# 03_MCU.net
KiCad netlist of a schematic drawn in Altium Designer
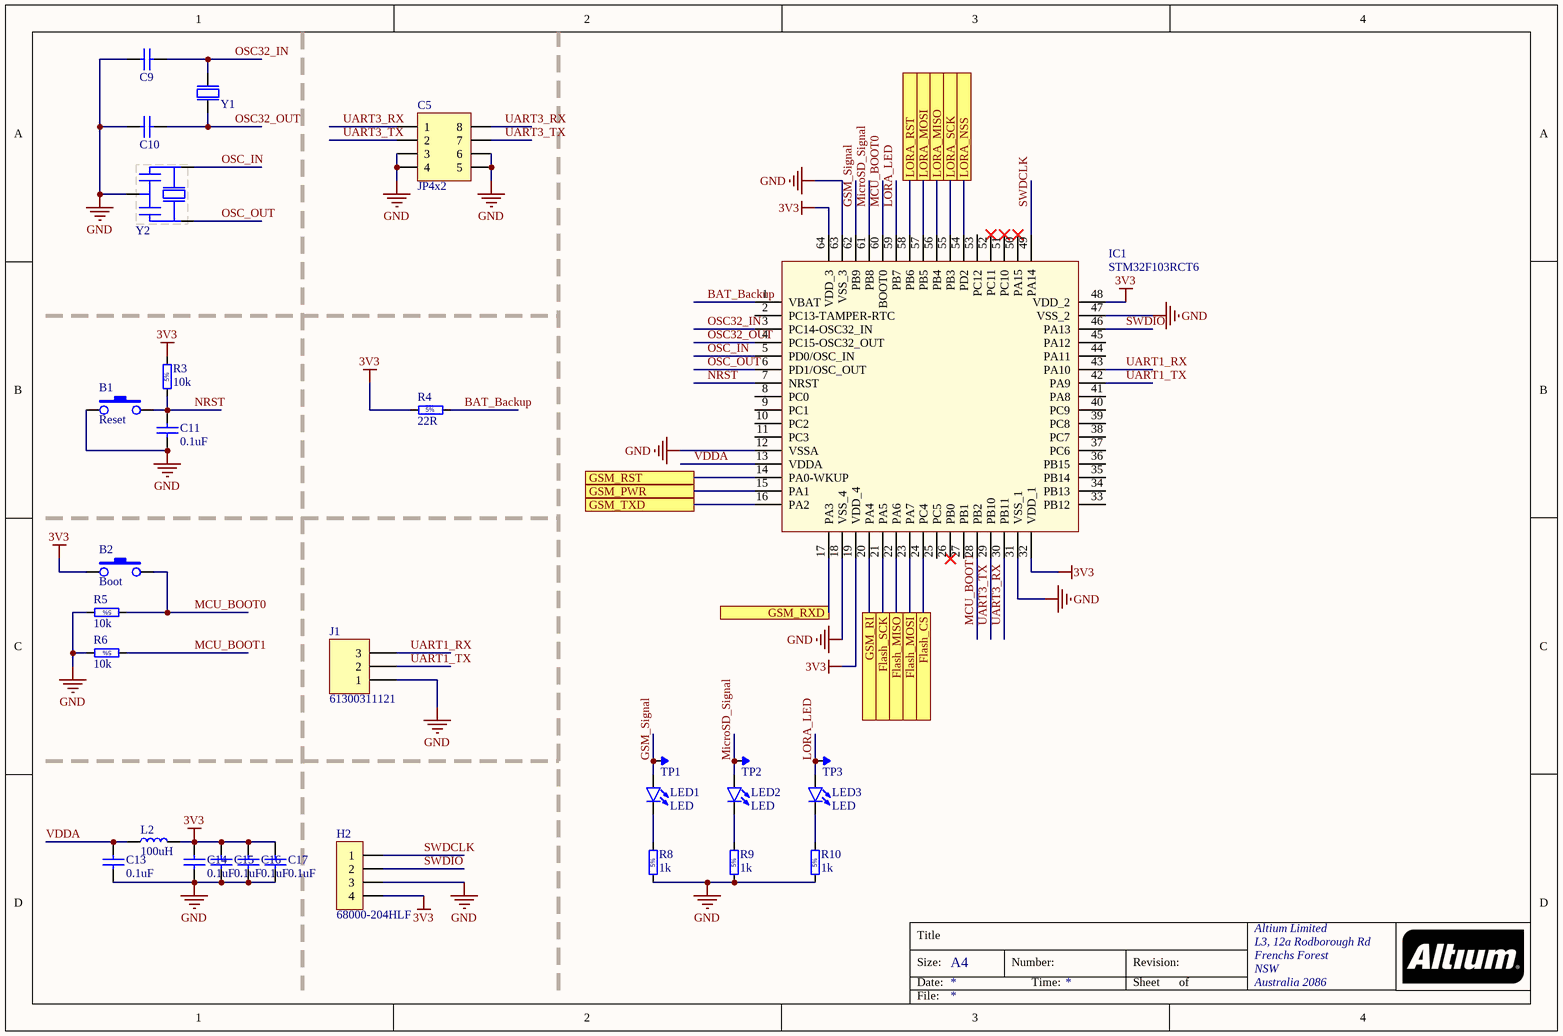
[diagram p0: [03].MCU.SchDoc]

(export (version "E")
  (design (tool "Eeschema 10.0.6"))
  (components
    (comp (ref "B1")
      (value "Reset")
      (footprint "TACTILE-SWITCH-1101NE")
      (libsource (lib "ThanhNT") (part "Button_2P_SMD"))
    )
    (comp (ref "B2")
      (value "Boot")
      (footprint "TACTILE-SWITCH-1101NE")
      (libsource (lib "ThanhNT") (part "Button_2P_SMD"))
    )
    (comp (ref "C5")
      (value "JP4x2")
      (footprint "JP4-D2T")
      (description "WR-PHD 2.54 mm Dual Socket Header")
      (fields
        (field (name "MANUFACTURER") "Würth Elektronik eiSos GmbH")
        (field (name "PARTNO") "61300821821")
        (field (name "CREATED BY") "Karrer Zheng")
      )
      (libsource (lib "LIBRARY") (part "JP4x2"))
    )
    (comp (ref "C9")
      (value "10pF")
      (footprint "C_0603")
      (description "Non-polarised capacitor")
      (fields (field (name "PART NUMBER") "VJ0805A100JXJPW1BC") (field (name "VOLTAGE") "16VDC"))
      (libsource (lib "Capacitors") (part "Capacitor - non polarized"))
    )
    (comp (ref "C10")
      (value "10pF")
      (footprint "C_0603")
      (description "Non-polarised capacitor")
      (fields (field (name "PART NUMBER") "VJ0805A100JXJPW1BC") (field (name "VOLTAGE") "16VDC"))
      (libsource (lib "Capacitors") (part "Capacitor - non polarized"))
    )
    (comp (ref "C11")
      (value "0.1uF")
      (footprint "C_0603")
      (description "Non-polarised capacitor")
      (fields (field (name "PART NUMBER") "VJ0805Y104KXXMC") (field (name "VOLTAGE") "25VDC"))
      (libsource (lib "Capacitors") (part "Capacitor - non polarized"))
    )
    (comp (ref "C13")
      (value "0.1uF")
      (footprint "C_0603")
      (description "Non-polarised capacitor")
      (fields (field (name "PART NUMBER") "VJ0805Y104KXXMC") (field (name "VOLTAGE") "25VDC"))
      (libsource (lib "Capacitors") (part "Capacitor - non polarized"))
    )
    (comp (ref "C14")
      (value "0.1uF")
      (footprint "C_0603")
      (description "Non-polarised capacitor")
      (fields (field (name "PART NUMBER") "VJ0805Y104KXXMC") (field (name "VOLTAGE") "25VDC"))
      (libsource (lib "Capacitors") (part "Capacitor - non polarized"))
    )
    (comp (ref "C15")
      (value "0.1uF")
      (footprint "C_0603")
      (description "Non-polarised capacitor")
      (fields (field (name "PART NUMBER") "VJ0805Y104KXXMC") (field (name "VOLTAGE") "25VDC"))
      (libsource (lib "Capacitors") (part "Capacitor - non polarized"))
    )
    (comp (ref "C16")
      (value "0.1uF")
      (footprint "C_0603")
      (description "Non-polarised capacitor")
      (fields (field (name "PART NUMBER") "VJ0805Y104KXXMC") (field (name "VOLTAGE") "25VDC"))
      (libsource (lib "Capacitors") (part "Capacitor - non polarized"))
    )
    (comp (ref "C17")
      (value "0.1uF")
      (footprint "C_0603")
      (description "Non-polarised capacitor")
      (fields (field (name "PART NUMBER") "VJ0805Y104KXXMC") (field (name "VOLTAGE") "25VDC"))
      (libsource (lib "Capacitors") (part "Capacitor - non polarized"))
    )
    (comp (ref "H2")
      (value "68000-204HLF")
      (footprint "HDR1X4")
      (description "CONN HEADER 4POS .100 STR 15AU")
      (fields
        (field (name "DEVICE") "68000-204HLF")
        (field (name "MANUFACTURER") "Amphenol FCI")
        (field (name "AUTHOR") "MDBK")
      )
      (libsource (lib "Eletro-mechanical") (part "Header_4p_2.54mm"))
    )
    (comp (ref "IC1")
      (value "STM32F103RCT6")
      (footprint "QFP50P1000X1000X160-64N")
      (description "ARM Microcontrollers - MCU 32BIT Cortex M3 H/D 256 to 512 USB/CAN")
      (fields
        (field (name "DEVICE") "STM32F103RCT6")
        (field (name "MANUFACTURER") "STMicroelectronics")
        (field (name "AUTHOR") "MDBK")
      )
      (libsource (lib "ICs And Semiconductors") (part "STM32F103RCT"))
    )
    (comp (ref "J1")
      (value "61300311121")
      (footprint "HDR1X3")
      (description "CONN HEADER 3 POS 2.54")
      (fields
        (field (name "DEVICE") "61300311121")
        (field (name "MANUFACTURER") "Wurth Electronics Inc.")
        (field (name "AUTHOR") "MDBK")
      )
      (libsource (lib "Eletro-mechanical") (part "Header_3p_2.54mm"))
    )
    (comp (ref "L2")
      (value "100uH")
      (footprint "Inductor_0805")
      (description "FIXED IND 100UH 80MA 5.5 OHM SMD")
      (fields
        (field (name "PART NUMBER") "LB2016T101M")
        (field (name "MANUFACTURER") "Taiyo Yuden")
        (field (name "AUTHOR") "MDBK")
      )
      (libsource (lib "Inductors & Transformers") (part "GLFR1608T101M-LR"))
    )
    (comp (ref "LED1") (value "LED") (footprint "LED_0805") (libsource (lib "ThanhNT") (part "LED_0805")))
    (comp (ref "LED2") (value "LED") (footprint "LED_0805") (libsource (lib "ThanhNT") (part "LED_0805")))
    (comp (ref "LED3") (value "LED") (footprint "LED_0805") (libsource (lib "ThanhNT") (part "LED_0805")))
    (comp (ref "R3")
      (value "10k")
      (footprint "R_0603")
      (description "Resistor - 5%")
      (fields
        (field (name "PART NUMBER") "RC0805FR-0710KL")
        (field (name "POWER") "125 mW (1/8 W)")
        (field (name "AUTHOR") "MDBK")
      )
      (libsource (lib "Resistors") (part "Resistor - 5%"))
    )
    (comp (ref "R4")
      (value "22R")
      (footprint "R_0603")
      (description "Resistor - 5%")
      (fields
        (field (name "PART NUMBER") "RC0805FR-0722RL")
        (field (name "POWER") "125 mW (1/8 W)")
        (field (name "AUTHOR") "MDBK")
      )
      (libsource (lib "Resistors") (part "Resistor - 5%"))
    )
    (comp (ref "R5")
      (value "10k")
      (footprint "R_0603")
      (description "Resistor - 5%")
      (fields
        (field (name "PART NUMBER") "RC0805FR-0710KL")
        (field (name "POWER") "125 mW (1/8 W)")
        (field (name "AUTHOR") "MDBK")
      )
      (libsource (lib "Resistors") (part "Resistor - 5%"))
    )
    (comp (ref "R6")
      (value "10k")
      (footprint "R_0603")
      (description "Resistor - 5%")
      (fields
        (field (name "PART NUMBER") "RC0805FR-0710KL")
        (field (name "POWER") "125 mW (1/8 W)")
        (field (name "AUTHOR") "MDBK")
      )
      (libsource (lib "Resistors") (part "Resistor - 5%"))
    )
    (comp (ref "R8")
      (value "1k")
      (footprint "R_0603")
      (description "Resistor - 5%")
      (fields
        (field (name "PART NUMBER") "RC0805JR-071KL")
        (field (name "POWER") "125 mW (1/8 W)")
        (field (name "AUTHOR") "MDBK")
      )
      (libsource (lib "Resistors") (part "Resistor - 5%"))
    )
    (comp (ref "R9")
      (value "1k")
      (footprint "R_0603")
      (description "Resistor - 5%")
      (fields
        (field (name "PART NUMBER") "RC0805JR-071KL")
        (field (name "POWER") "125 mW (1/8 W)")
        (field (name "AUTHOR") "MDBK")
      )
      (libsource (lib "Resistors") (part "Resistor - 5%"))
    )
    (comp (ref "R10")
      (value "1k")
      (footprint "R_0603")
      (description "Resistor - 5%")
      (fields
        (field (name "PART NUMBER") "RC0805JR-071KL")
        (field (name "POWER") "125 mW (1/8 W)")
        (field (name "AUTHOR") "MDBK")
      )
      (libsource (lib "Resistors") (part "Resistor - 5%"))
    )
    (comp (ref "TP1") (value "TESTPOINT") (footprint "TP-R40") (libsource (lib "ThanhNT") (part "TESTPOINT")))
    (comp (ref "TP2") (value "TESTPOINT") (footprint "TP-R40") (libsource (lib "ThanhNT") (part "TESTPOINT")))
    (comp (ref "TP3") (value "TESTPOINT") (footprint "TP-R40") (libsource (lib "ThanhNT") (part "TESTPOINT")))
    (comp (ref "Y1")
      (value "FC-135 32.7680KA-A0")
      (footprint "Crystal_2P")
      (description "CRYSTAL 32.7680KHZ 12.5PF SMT")
      (fields (field (name "MANUFACTURER") "EPSON") (field (name "AUTHOR") "MDBK"))
      (libsource (lib "Eletro-mechanical") (part "Crystal_32k"))
    )
    (comp (ref "Y2")
      (value "CSTCE8M00G52-R0")
      (footprint "Crystal_4P")
      (description "CER RES 8.0000MHZ 10PF SMD")
      (fields (field (name "MANUFACTURER") "Murata Electronics North America") (field (name "AUTHOR") "MDBK"))
      (libsource (lib "Eletro-mechanical") (part "Crystal-8MHz"))
    )
  )
  (nets
    (net (code "1") (name "/BAT_Backup") (class "Default")
      (node (ref "IC1") (pin "1") (pinfunction "VBAT_1") (pintype "passive"))
      (node (ref "R4") (pin "2") (pinfunction "2_2") (pintype "passive"))
    )
    (net (code "2") (name "/Flash_CS") (class "Default")
      (node (ref "IC1") (pin "24") (pinfunction "PC4_24") (pintype "passive"))
    )
    (net (code "3") (name "/Flash_MISO") (class "Default")
      (node (ref "IC1") (pin "22") (pinfunction "PA6_22") (pintype "passive"))
    )
    (net (code "4") (name "/Flash_MOSI") (class "Default")
      (node (ref "IC1") (pin "23") (pinfunction "PA7_23") (pintype "passive"))
    )
    (net (code "5") (name "/Flash_SCK") (class "Default")
      (node (ref "IC1") (pin "21") (pinfunction "PA5_21") (pintype "passive"))
    )
    (net (code "6") (name "/GSM_PWR") (class "Default")
      (node (ref "IC1") (pin "15") (pinfunction "PA1_15") (pintype "passive"))
    )
    (net (code "7") (name "/GSM_RI") (class "Default")
      (node (ref "IC1") (pin "20") (pinfunction "PA4_20") (pintype "passive"))
    )
    (net (code "8") (name "/GSM_RST") (class "Default")
      (node (ref "IC1") (pin "14") (pinfunction "PA0-WKUP_14") (pintype "passive"))
    )
    (net (code "9") (name "/GSM_RXD") (class "Default")
      (node (ref "IC1") (pin "17") (pinfunction "PA3_17") (pintype "passive"))
    )
    (net (code "10") (name "/GSM_Signal") (class "Default")
      (node (ref "IC1") (pin "62") (pinfunction "PB9_62") (pintype "passive"))
      (node (ref "LED1") (pin "A") (pinfunction "A_A") (pintype "passive"))
      (node (ref "TP1") (pin "1") (pintype "passive"))
    )
    (net (code "11") (name "/GSM_TXD") (class "Default")
      (node (ref "IC1") (pin "16") (pinfunction "PA2_16") (pintype "passive"))
    )
    (net (code "12") (name "/LORA_LED") (class "Default")
      (node (ref "IC1") (pin "59") (pinfunction "PB7_59") (pintype "passive"))
      (node (ref "LED3") (pin "A") (pinfunction "A_A") (pintype "passive"))
      (node (ref "TP3") (pin "1") (pintype "passive"))
    )
    (net (code "13") (name "/LORA_MISO") (class "Default")
      (node (ref "IC1") (pin "56") (pinfunction "PB4_56") (pintype "passive"))
    )
    (net (code "14") (name "/LORA_MOSI") (class "Default")
      (node (ref "IC1") (pin "57") (pinfunction "PB5_57") (pintype "passive"))
    )
    (net (code "15") (name "/LORA_NSS") (class "Default")
      (node (ref "IC1") (pin "54") (pinfunction "PD2_54") (pintype "passive"))
    )
    (net (code "16") (name "/LORA_RST") (class "Default")
      (node (ref "IC1") (pin "58") (pinfunction "PB6_58") (pintype "passive"))
    )
    (net (code "17") (name "/LORA_SCK") (class "Default")
      (node (ref "IC1") (pin "55") (pinfunction "PB3_55") (pintype "passive"))
    )
    (net (code "18") (name "/MCU_BOOT0") (class "Default")
      (node (ref "B2") (pin "2") (pinfunction "2_2") (pintype "passive"))
      (node (ref "IC1") (pin "60") (pinfunction "BOOT0_60") (pintype "passive"))
      (node (ref "R5") (pin "1") (pinfunction "1_1") (pintype "passive"))
    )
    (net (code "19") (name "/MCU_BOOT1") (class "Default")
      (node (ref "IC1") (pin "28") (pinfunction "PB2_28") (pintype "passive"))
      (node (ref "R6") (pin "1") (pinfunction "1_1") (pintype "passive"))
    )
    (net (code "20") (name "/MicroSD_Signal") (class "Default")
      (node (ref "IC1") (pin "61") (pinfunction "PB8_61") (pintype "passive"))
      (node (ref "LED2") (pin "A") (pinfunction "A_A") (pintype "passive"))
      (node (ref "TP2") (pin "1") (pintype "passive"))
    )
    (net (code "21") (name "/NRST") (class "Default")
      (node (ref "B1") (pin "2") (pinfunction "2_2") (pintype "passive"))
      (node (ref "C11") (pin "2") (pinfunction "2_2") (pintype "passive"))
      (node (ref "IC1") (pin "7") (pinfunction "NRST_7") (pintype "passive"))
      (node (ref "R3") (pin "1") (pinfunction "1_1") (pintype "passive"))
    )
    (net (code "22") (name "/OSC32_IN") (class "Default")
      (node (ref "C9") (pin "2") (pinfunction "2_2") (pintype "passive"))
      (node (ref "IC1") (pin "3") (pinfunction "PC14-OSC32_IN_3") (pintype "passive"))
      (node (ref "Y1") (pin "2") (pintype "passive"))
    )
    (net (code "23") (name "/OSC32_OUT") (class "Default")
      (node (ref "C10") (pin "2") (pinfunction "2_2") (pintype "passive"))
      (node (ref "IC1") (pin "4") (pinfunction "PC15-OSC32_OUT_4") (pintype "passive"))
      (node (ref "Y1") (pin "1") (pintype "passive"))
    )
    (net (code "24") (name "/OSC_IN") (class "Default")
      (node (ref "IC1") (pin "5") (pinfunction "PD0/OSC_IN_5") (pintype "passive"))
      (node (ref "Y2") (pin "1") (pinfunction "1_1") (pintype "passive"))
    )
    (net (code "25") (name "/OSC_OUT") (class "Default")
      (node (ref "IC1") (pin "6") (pinfunction "PD1/OSC_OUT_6") (pintype "passive"))
      (node (ref "Y2") (pin "3") (pinfunction "3_3") (pintype "passive"))
    )
    (net (code "26") (name "/SWDCLK") (class "Default")
      (node (ref "H2") (pin "1") (pinfunction "1_1") (pintype "passive"))
      (node (ref "IC1") (pin "49") (pinfunction "PA14_49") (pintype "passive"))
    )
    (net (code "27") (name "/SWDIO") (class "Default")
      (node (ref "H2") (pin "2") (pinfunction "2_2") (pintype "passive"))
      (node (ref "IC1") (pin "46") (pinfunction "PA13_46") (pintype "passive"))
    )
    (net (code "28") (name "/UART1_RX") (class "Default")
      (node (ref "IC1") (pin "43") (pinfunction "PA10_43") (pintype "passive"))
      (node (ref "J1") (pin "3") (pinfunction "3_3") (pintype "passive"))
    )
    (net (code "29") (name "/UART1_TX") (class "Default")
      (node (ref "IC1") (pin "42") (pinfunction "PA9_42") (pintype "passive"))
      (node (ref "J1") (pin "2") (pinfunction "2_2") (pintype "passive"))
    )
    (net (code "30") (name "/UART3_RX") (class "Default")
      (node (ref "C5") (pin "1") (pinfunction "1_1") (pintype "passive"))
      (node (ref "C5") (pin "8") (pinfunction "8_8") (pintype "passive"))
      (node (ref "IC1") (pin "30") (pinfunction "PB11_30") (pintype "passive"))
    )
    (net (code "31") (name "/UART3_TX") (class "Default")
      (node (ref "C5") (pin "2") (pinfunction "2_2") (pintype "passive"))
      (node (ref "C5") (pin "7") (pinfunction "7_7") (pintype "passive"))
      (node (ref "IC1") (pin "29") (pinfunction "PB10_29") (pintype "passive"))
    )
    (net (code "32") (name "/VDDA") (class "Default")
      (node (ref "C13") (pin "2") (pinfunction "2_2") (pintype "passive"))
      (node (ref "IC1") (pin "13") (pinfunction "VDDA_13") (pintype "passive"))
      (node (ref "L2") (pin "1") (pinfunction "1_1") (pintype "passive"))
    )
    (net (code "33") (name "3V3") (class "Default")
      (node (ref "B2") (pin "1") (pinfunction "1_1") (pintype "passive"))
      (node (ref "C14") (pin "2") (pinfunction "2_2") (pintype "passive"))
      (node (ref "C15") (pin "2") (pinfunction "2_2") (pintype "passive"))
      (node (ref "C16") (pin "2") (pinfunction "2_2") (pintype "passive"))
      (node (ref "C17") (pin "2") (pinfunction "2_2") (pintype "passive"))
      (node (ref "H2") (pin "4") (pinfunction "4_4") (pintype "passive"))
      (node (ref "IC1") (pin "19") (pinfunction "VDD_4_19") (pintype "passive"))
      (node (ref "IC1") (pin "32") (pinfunction "VDD_1_32") (pintype "passive"))
      (node (ref "IC1") (pin "48") (pinfunction "VDD_2_48") (pintype "passive"))
      (node (ref "IC1") (pin "64") (pinfunction "VDD_3_64") (pintype "passive"))
      (node (ref "L2") (pin "2") (pinfunction "2_2") (pintype "passive"))
      (node (ref "R3") (pin "2") (pinfunction "2_2") (pintype "passive"))
      (node (ref "R4") (pin "1") (pinfunction "1_1") (pintype "passive"))
    )
    (net (code "34") (name "GND") (class "Default")
      (node (ref "B1") (pin "1") (pinfunction "1_1") (pintype "passive"))
      (node (ref "C10") (pin "1") (pinfunction "1_1") (pintype "passive"))
      (node (ref "C11") (pin "1") (pinfunction "1_1") (pintype "passive"))
      (node (ref "C13") (pin "1") (pinfunction "1_1") (pintype "passive"))
      (node (ref "C14") (pin "1") (pinfunction "1_1") (pintype "passive"))
      (node (ref "C15") (pin "1") (pinfunction "1_1") (pintype "passive"))
      (node (ref "C16") (pin "1") (pinfunction "1_1") (pintype "passive"))
      (node (ref "C17") (pin "1") (pinfunction "1_1") (pintype "passive"))
      (node (ref "C5") (pin "3") (pinfunction "3_3") (pintype "passive"))
      (node (ref "C5") (pin "4") (pinfunction "4_4") (pintype "passive"))
      (node (ref "C5") (pin "5") (pinfunction "5_5") (pintype "passive"))
      (node (ref "C5") (pin "6") (pinfunction "6_6") (pintype "passive"))
      (node (ref "C9") (pin "1") (pinfunction "1_1") (pintype "passive"))
      (node (ref "H2") (pin "3") (pinfunction "3_3") (pintype "passive"))
      (node (ref "IC1") (pin "12") (pinfunction "VSSA_12") (pintype "passive"))
      (node (ref "IC1") (pin "18") (pinfunction "VSS_4_18") (pintype "passive"))
      (node (ref "IC1") (pin "31") (pinfunction "VSS_1_31") (pintype "passive"))
      (node (ref "IC1") (pin "47") (pinfunction "VSS_2_47") (pintype "passive"))
      (node (ref "IC1") (pin "63") (pinfunction "VSS_3_63") (pintype "passive"))
      (node (ref "J1") (pin "1") (pinfunction "1_1") (pintype "passive"))
      (node (ref "R10") (pin "1") (pinfunction "1_1") (pintype "passive"))
      (node (ref "R5") (pin "2") (pinfunction "2_2") (pintype "passive"))
      (node (ref "R6") (pin "2") (pinfunction "2_2") (pintype "passive"))
      (node (ref "R8") (pin "1") (pinfunction "1_1") (pintype "passive"))
      (node (ref "R9") (pin "1") (pinfunction "1_1") (pintype "passive"))
      (node (ref "Y2") (pin "2") (pinfunction "2_2") (pintype "passive"))
    )
    (net (code "35") (name "Net-(LED1-PadK)") (class "Default")
      (node (ref "LED1") (pin "K") (pinfunction "K_K") (pintype "passive"))
      (node (ref "R8") (pin "2") (pinfunction "2_2") (pintype "passive"))
    )
    (net (code "36") (name "Net-(LED2-PadK)") (class "Default")
      (node (ref "LED2") (pin "K") (pinfunction "K_K") (pintype "passive"))
      (node (ref "R9") (pin "2") (pinfunction "2_2") (pintype "passive"))
    )
    (net (code "37") (name "Net-(LED3-PadK)") (class "Default")
      (node (ref "LED3") (pin "K") (pinfunction "K_K") (pintype "passive"))
      (node (ref "R10") (pin "2") (pinfunction "2_2") (pintype "passive"))
    )
    (net (code "38") (name "unconnected-(IC1-PA8-Pad41)") (class "Default")
      (node (ref "IC1") (pin "41") (pinfunction "PA8_41") (pintype "passive"))
    )
    (net (code "39") (name "unconnected-(IC1-PA11-Pad44)") (class "Default")
      (node (ref "IC1") (pin "44") (pinfunction "PA11_44") (pintype "passive"))
    )
    (net (code "40") (name "unconnected-(IC1-PA12-Pad45)") (class "Default")
      (node (ref "IC1") (pin "45") (pinfunction "PA12_45") (pintype "passive"))
    )
    (net (code "41") (name "unconnected-(IC1-PA15-Pad50)") (class "Default")
      (node (ref "IC1") (pin "50") (pinfunction "PA15_50") (pintype "passive+no_connect"))
    )
    (net (code "42") (name "unconnected-(IC1-PB0-Pad26)") (class "Default")
      (node (ref "IC1") (pin "26") (pinfunction "PB0_26") (pintype "passive+no_connect"))
    )
    (net (code "43") (name "unconnected-(IC1-PB1-Pad27)") (class "Default")
      (node (ref "IC1") (pin "27") (pinfunction "PB1_27") (pintype "passive"))
    )
    (net (code "44") (name "unconnected-(IC1-PB12-Pad33)") (class "Default")
      (node (ref "IC1") (pin "33") (pinfunction "PB12_33") (pintype "passive"))
    )
    (net (code "45") (name "unconnected-(IC1-PB13-Pad34)") (class "Default")
      (node (ref "IC1") (pin "34") (pinfunction "PB13_34") (pintype "passive"))
    )
    (net (code "46") (name "unconnected-(IC1-PB14-Pad35)") (class "Default")
      (node (ref "IC1") (pin "35") (pinfunction "PB14_35") (pintype "passive"))
    )
    (net (code "47") (name "unconnected-(IC1-PB15-Pad36)") (class "Default")
      (node (ref "IC1") (pin "36") (pinfunction "PB15_36") (pintype "passive"))
    )
    (net (code "48") (name "unconnected-(IC1-PC0-Pad8)") (class "Default")
      (node (ref "IC1") (pin "8") (pinfunction "PC0_8") (pintype "passive"))
    )
    (net (code "49") (name "unconnected-(IC1-PC1-Pad9)") (class "Default")
      (node (ref "IC1") (pin "9") (pinfunction "PC1_9") (pintype "passive"))
    )
    (net (code "50") (name "unconnected-(IC1-PC2-Pad10)") (class "Default")
      (node (ref "IC1") (pin "10") (pinfunction "PC2_10") (pintype "passive"))
    )
    (net (code "51") (name "unconnected-(IC1-PC3-Pad11)") (class "Default")
      (node (ref "IC1") (pin "11") (pinfunction "PC3_11") (pintype "passive"))
    )
    (net (code "52") (name "unconnected-(IC1-PC5-Pad25)") (class "Default")
      (node (ref "IC1") (pin "25") (pinfunction "PC5_25") (pintype "passive"))
    )
    (net (code "53") (name "unconnected-(IC1-PC6-Pad37)") (class "Default")
      (node (ref "IC1") (pin "37") (pinfunction "PC6_37") (pintype "passive"))
    )
    (net (code "54") (name "unconnected-(IC1-PC7-Pad38)") (class "Default")
      (node (ref "IC1") (pin "38") (pinfunction "PC7_38") (pintype "passive"))
    )
    (net (code "55") (name "unconnected-(IC1-PC8-Pad39)") (class "Default")
      (node (ref "IC1") (pin "39") (pinfunction "PC8_39") (pintype "passive"))
    )
    (net (code "56") (name "unconnected-(IC1-PC9-Pad40)") (class "Default")
      (node (ref "IC1") (pin "40") (pinfunction "PC9_40") (pintype "passive"))
    )
    (net (code "57") (name "unconnected-(IC1-PC10-Pad51)") (class "Default")
      (node (ref "IC1") (pin "51") (pinfunction "PC10_51") (pintype "passive+no_connect"))
    )
    (net (code "58") (name "unconnected-(IC1-PC11-Pad52)") (class "Default")
      (node (ref "IC1") (pin "52") (pinfunction "PC11_52") (pintype "passive+no_connect"))
    )
    (net (code "59") (name "unconnected-(IC1-PC12-Pad53)") (class "Default")
      (node (ref "IC1") (pin "53") (pinfunction "PC12_53") (pintype "passive"))
    )
    (net (code "60") (name "unconnected-(IC1-PC13-TAMPER-RTC-Pad2)") (class "Default")
      (node (ref "IC1") (pin "2") (pinfunction "PC13-TAMPER-RTC_2") (pintype "passive"))
    )
  )
)
